# Amplifier.net
KiCad netlist of a schematic drawn in Altium Designer
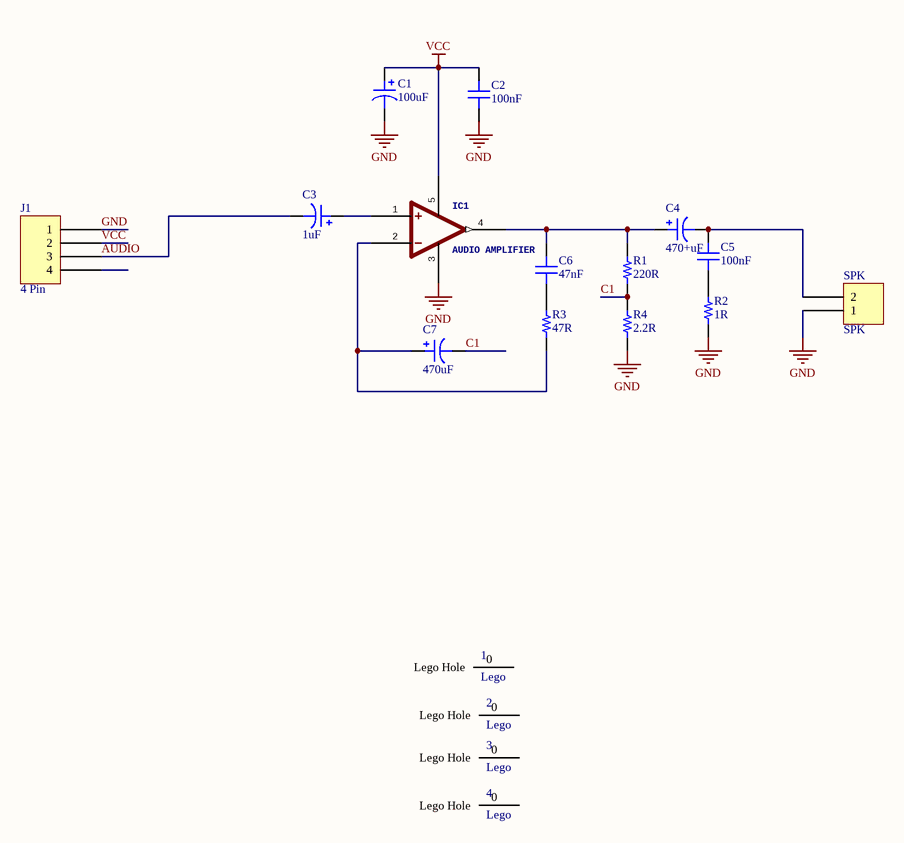
[diagram p0: Amplifier.SchDoc]

(export (version "E")
  (design (tool "Eeschema 10.0.6"))
  (components
    (comp (ref "1") (value "Lego") (footprint "Lego Hole") (libsource (lib "Connectors") (part "Lego")))
    (comp (ref "2") (value "Lego") (footprint "Lego Hole") (libsource (lib "Connectors") (part "Lego")))
    (comp (ref "3") (value "Lego") (footprint "Lego Hole") (libsource (lib "Connectors") (part "Lego")))
    (comp (ref "4") (value "Lego") (footprint "Lego Hole") (libsource (lib "Connectors") (part "Lego")))
    (comp (ref "C1")
      (value "100uF")
      (footprint "CAP ALUM 5MM")
      (description "SMT Polarised Capacitor")
      (libsource (lib "") (part "Polarised Capacitor_1"))
    )
    (comp (ref "C2")
      (value "100nF")
      (footprint "CAP 1206/3216")
      (description "SMT Capacitor")
      (libsource (lib "Cap_Res") (part "Capacitor"))
    )
    (comp (ref "C3")
      (value "1uF")
      (footprint "CAP ALUM 5MM")
      (description "SMT Polarised Capacitor")
      (libsource (lib "Cap_Res") (part "Polarised Capacitor"))
    )
    (comp (ref "C4")
      (value "470+uF")
      (footprint "CAP ALUM 5MM")
      (description "SMT Polarised Capacitor")
      (libsource (lib "Cap_Res") (part "Polarised Capacitor"))
    )
    (comp (ref "C5")
      (value "100nF")
      (footprint "CAP 1206/3216")
      (description "SMT Capacitor")
      (libsource (lib "Cap_Res") (part "Capacitor"))
    )
    (comp (ref "C6")
      (value "47nF")
      (footprint "CAP 1206/3216")
      (description "SMT Capacitor")
      (libsource (lib "Cap_Res") (part "Capacitor"))
    )
    (comp (ref "C7")
      (value "470uF")
      (footprint "CAP ALUM 5MM")
      (description "SMT Polarised Capacitor")
      (libsource (lib "Cap_Res") (part "Polarised Capacitor"))
    )
    (comp (ref "IC1")
      (value "AUDIO AMPLIFIER")
      (footprint "TDA2003")
      (fields (field (name "MF") "Vishay Semiconductor") (field (name "MP") "TDA2003"))
      (libsource (lib "Other") (part "TDA2003V"))
    )
    (comp (ref "J1")
      (value "4 Pin")
      (footprint "JST XH B4B-XH-A - RIGHT")
      (libsource (lib "Connectors") (part "4 Pin"))
    )
    (comp (ref "R1")
      (value "220R")
      (footprint "RES 1206/3216")
      (description "SMT Resistor")
      (libsource (lib "Cap_Res") (part "Resistor"))
    )
    (comp (ref "R2")
      (value "1R")
      (footprint "RES 1206/3216")
      (description "SMT Resistor")
      (libsource (lib "Cap_Res") (part "Resistor"))
    )
    (comp (ref "R3")
      (value "47R")
      (footprint "RES 1206/3216")
      (description "SMT Resistor")
      (libsource (lib "Cap_Res") (part "Resistor"))
    )
    (comp (ref "R4")
      (value "2.2R")
      (footprint "RES 1206/3216")
      (description "SMT Resistor")
      (libsource (lib "Cap_Res") (part "Resistor"))
    )
    (comp (ref "SPK") (value "SPK") (footprint "Socket_Blue_2") (libsource (lib "Connectors") (part "2 Pin")))
  )
  (nets
    (net (code "1") (name "/AUDIO") (class "Default")
      (node (ref "C3") (pin "2") (pinfunction "2_2") (pintype "passive"))
      (node (ref "J1") (pin "3") (pinfunction "3_3") (pintype "passive"))
    )
    (net (code "2") (name "/C1") (class "Default")
      (node (ref "C7") (pin "2") (pinfunction "2_2") (pintype "passive"))
      (node (ref "R1") (pin "1") (pinfunction "1_1") (pintype "passive"))
      (node (ref "R4") (pin "2") (pinfunction "2_2") (pintype "passive"))
    )
    (net (code "3") (name "GND") (class "Default")
      (node (ref "C1") (pin "2") (pinfunction "2_2") (pintype "passive"))
      (node (ref "C2") (pin "1") (pinfunction "1_1") (pintype "passive"))
      (node (ref "IC1") (pin "3") (pinfunction "GND_3") (pintype "power_in"))
      (node (ref "J1") (pin "1") (pinfunction "1_1") (pintype "passive"))
      (node (ref "R2") (pin "1") (pinfunction "1_1") (pintype "passive"))
      (node (ref "R4") (pin "1") (pinfunction "1_1") (pintype "passive"))
      (node (ref "SPK") (pin "1") (pinfunction "1_1") (pintype "passive"))
    )
    (net (code "4") (name "Net-(C4-Pad2)") (class "Default")
      (node (ref "C4") (pin "2") (pinfunction "2_2") (pintype "passive"))
      (node (ref "C5") (pin "2") (pinfunction "2_2") (pintype "passive"))
      (node (ref "SPK") (pin "2") (pinfunction "2_2") (pintype "passive"))
    )
    (net (code "5") (name "Net-(C5-Pad1)") (class "Default")
      (node (ref "C5") (pin "1") (pinfunction "1_1") (pintype "passive"))
      (node (ref "R2") (pin "2") (pinfunction "2_2") (pintype "passive"))
    )
    (net (code "6") (name "Net-(C6-Pad1)") (class "Default")
      (node (ref "C6") (pin "1") (pinfunction "1_1") (pintype "passive"))
      (node (ref "R3") (pin "2") (pinfunction "2_2") (pintype "passive"))
    )
    (net (code "7") (name "Net-(IC1-+IN)") (class "Default")
      (node (ref "C3") (pin "1") (pinfunction "1_1") (pintype "passive"))
      (node (ref "IC1") (pin "1") (pinfunction "+IN_1") (pintype "passive"))
    )
    (net (code "8") (name "Net-(IC1--IN)") (class "Default")
      (node (ref "C7") (pin "1") (pinfunction "1_1") (pintype "passive"))
      (node (ref "IC1") (pin "2") (pinfunction "-IN_2") (pintype "passive"))
      (node (ref "R3") (pin "1") (pinfunction "1_1") (pintype "passive"))
    )
    (net (code "9") (name "Net-(IC1-OUT)") (class "Default")
      (node (ref "C4") (pin "1") (pinfunction "1_1") (pintype "passive"))
      (node (ref "C6") (pin "2") (pinfunction "2_2") (pintype "passive"))
      (node (ref "IC1") (pin "4") (pinfunction "OUT_4") (pintype "output"))
      (node (ref "R1") (pin "2") (pinfunction "2_2") (pintype "passive"))
    )
    (net (code "10") (name "VCC") (class "Default")
      (node (ref "C1") (pin "1") (pinfunction "1_1") (pintype "passive"))
      (node (ref "C2") (pin "2") (pinfunction "2_2") (pintype "passive"))
      (node (ref "IC1") (pin "5") (pinfunction "V+_5") (pintype "power_in"))
      (node (ref "J1") (pin "2") (pinfunction "2_2") (pintype "passive"))
    )
    (net (code "11") (name "unconnected-(1-Lego_Hole-Pad0)") (class "Default")
      (node (ref "1") (pin "0") (pinfunction "Lego_Hole_0") (pintype "passive"))
    )
    (net (code "12") (name "unconnected-(2-Lego_Hole-Pad0)") (class "Default")
      (node (ref "2") (pin "0") (pinfunction "Lego_Hole_0") (pintype "passive"))
    )
    (net (code "13") (name "unconnected-(3-Lego_Hole-Pad0)") (class "Default")
      (node (ref "3") (pin "0") (pinfunction "Lego_Hole_0") (pintype "passive"))
    )
    (net (code "14") (name "unconnected-(4-Lego_Hole-Pad0)") (class "Default")
      (node (ref "4") (pin "0") (pinfunction "Lego_Hole_0") (pintype "passive"))
    )
    (net (code "15") (name "unconnected-(J1-Pad4)") (class "Default")
      (node (ref "J1") (pin "4") (pinfunction "4_4") (pintype "passive"))
    )
  )
)
